# Schematic.net
KiCad netlist of a schematic drawn in Altium Designer
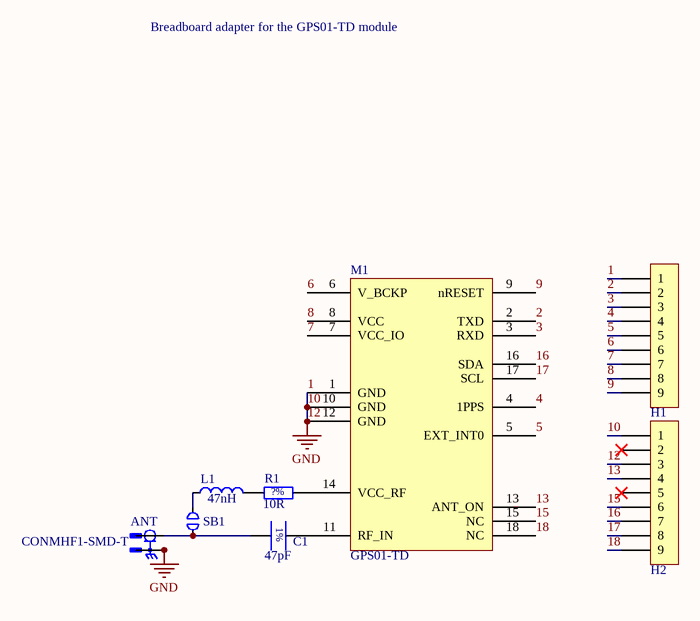
[diagram p0: Schematic.SchDoc]

(export (version "E")
  (design (tool "Eeschema 10.0.6"))
  (components
    (comp (ref "ANT")
      (value "CONMHF1-SMD-T")
      (footprint "TE_CONMHF1-SMD-T")
      (libsource (lib "CONMHF1-SMD-T") (part "CONMHF1-SMD-T"))
    )
    (comp (ref "C1")
      (value "47pF")
      (footprint "CAPACITOR_0805_2012M-70N")
      (description "Passive - Capacitor, Generic")
      (fields (field (name "TOLERANCE") "1%"))
      (libsource (lib "APSS Generic Components") (part "Generic Capacitor"))
    )
    (comp (ref "H1")
      (value "HDR,2.54mm,1x9")
      (footprint "APSS Connectors:HEADER_2.54MM_1x9PIN")
      (description "Connector - 2.54mm, 1x9-pin")
      (libsource (lib "APSS Connectors") (part "HDR,2.54mm,1x9"))
    )
    (comp (ref "H2")
      (value "HDR,2.54mm,1x9")
      (footprint "APSS Connectors:HEADER_2.54MM_1x9PIN")
      (description "Connector - 2.54mm, 1x9-pin")
      (libsource (lib "APSS Connectors") (part "HDR,2.54mm,1x9"))
    )
    (comp (ref "L1")
      (value "47nH")
      (footprint "APSS Generic Components:RESISTOR_0805_2012M-50N")
      (description "Passive - Inductor, Generic")
      (libsource (lib "APSS Generic Components") (part "Generic Inductor"))
    )
    (comp (ref "M1")
      (value "GPS01-TD")
      (footprint "GPS01-TD:GPS01-TD")
      (libsource (lib "GPS01-TD") (part "GPS01-TD"))
    )
    (comp (ref "R1")
      (value "10R")
      (footprint "RESISTOR_0805_2012M-50N")
      (description "Passive - Resistor, Generic")
      (fields (field (name "TOLERANCE") "?%"))
      (libsource (lib "APSS Generic Components") (part "Generic Resistor"))
    )
    (comp (ref "SB1")
      (value "Solder Jumper Normally Open")
      (footprint "APSS Generic Components:Solder Bridge Chevron 0402 Open")
      (libsource (lib "APSS Generic Components") (part "Solder Jumper Normally Open"))
    )
  )
  (nets
    (net (code "1") (name "/2") (class "Default")
      (node (ref "H1") (pin "2") (pinfunction "2_2") (pintype "passive"))
      (node (ref "M1") (pin "2") (pinfunction "TXD_2") (pintype "passive"))
    )
    (net (code "2") (name "/3") (class "Default")
      (node (ref "H1") (pin "3") (pinfunction "3_3") (pintype "passive"))
      (node (ref "M1") (pin "3") (pinfunction "RXD_3") (pintype "passive"))
    )
    (net (code "3") (name "/4") (class "Default")
      (node (ref "H1") (pin "4") (pinfunction "4_4") (pintype "passive"))
      (node (ref "M1") (pin "4") (pinfunction "1PPS_4") (pintype "passive"))
    )
    (net (code "4") (name "/5") (class "Default")
      (node (ref "H1") (pin "5") (pinfunction "5_5") (pintype "passive"))
      (node (ref "M1") (pin "5") (pinfunction "EXT_INT0_5") (pintype "passive"))
    )
    (net (code "5") (name "/6") (class "Default")
      (node (ref "H1") (pin "6") (pinfunction "6_6") (pintype "passive"))
      (node (ref "M1") (pin "6") (pinfunction "V_BCKP_6") (pintype "passive"))
    )
    (net (code "6") (name "/7") (class "Default")
      (node (ref "H1") (pin "7") (pinfunction "7_7") (pintype "passive"))
      (node (ref "M1") (pin "7") (pinfunction "VCC_IO_7") (pintype "passive"))
    )
    (net (code "7") (name "/8") (class "Default")
      (node (ref "H1") (pin "8") (pinfunction "8_8") (pintype "passive"))
      (node (ref "M1") (pin "8") (pinfunction "VCC_8") (pintype "passive"))
    )
    (net (code "8") (name "/9") (class "Default")
      (node (ref "H1") (pin "9") (pinfunction "9_9") (pintype "passive"))
      (node (ref "M1") (pin "9") (pinfunction "nRESET_9") (pintype "passive"))
    )
    (net (code "9") (name "/13") (class "Default")
      (node (ref "H2") (pin "4") (pinfunction "4_4") (pintype "passive"))
      (node (ref "M1") (pin "13") (pinfunction "ANT_ON_13") (pintype "passive"))
    )
    (net (code "10") (name "/15") (class "Default")
      (node (ref "H2") (pin "6") (pinfunction "6_6") (pintype "passive"))
      (node (ref "M1") (pin "15") (pinfunction "NC_15") (pintype "passive"))
    )
    (net (code "11") (name "/16") (class "Default")
      (node (ref "H2") (pin "7") (pinfunction "7_7") (pintype "passive"))
      (node (ref "M1") (pin "16") (pinfunction "SDA_16") (pintype "passive"))
    )
    (net (code "12") (name "/17") (class "Default")
      (node (ref "H2") (pin "8") (pinfunction "8_8") (pintype "passive"))
      (node (ref "M1") (pin "17") (pinfunction "SCL_17") (pintype "passive"))
    )
    (net (code "13") (name "/18") (class "Default")
      (node (ref "H2") (pin "9") (pinfunction "9_9") (pintype "passive"))
      (node (ref "M1") (pin "18") (pinfunction "NC_18") (pintype "passive"))
    )
    (net (code "14") (name "GND") (class "Default")
      (node (ref "ANT") (pin "2") (pinfunction "GND_2") (pintype "power_in"))
      (node (ref "ANT") (pin "3") (pinfunction "GND_3") (pintype "power_in"))
      (node (ref "ANT") (pin "4") (pinfunction "GND_4") (pintype "power_in"))
      (node (ref "H1") (pin "1") (pinfunction "1_1") (pintype "passive"))
      (node (ref "H2") (pin "1") (pinfunction "1_1") (pintype "passive"))
      (node (ref "H2") (pin "3") (pinfunction "3_3") (pintype "passive"))
      (node (ref "M1") (pin "1") (pinfunction "GND_1") (pintype "passive"))
      (node (ref "M1") (pin "10") (pinfunction "GND_10") (pintype "passive"))
      (node (ref "M1") (pin "12") (pinfunction "GND_12") (pintype "passive"))
    )
    (net (code "15") (name "Net-(ANT-SIG)") (class "Default")
      (node (ref "ANT") (pin "1") (pinfunction "SIG_1") (pintype "passive"))
      (node (ref "C1") (pin "1") (pinfunction "1_1") (pintype "passive"))
      (node (ref "SB1") (pin "2") (pinfunction "2_2") (pintype "passive"))
    )
    (net (code "16") (name "Net-(L1-Pad1)") (class "Default")
      (node (ref "L1") (pin "1") (pinfunction "1_1") (pintype "passive"))
      (node (ref "SB1") (pin "1") (pinfunction "1_1") (pintype "passive"))
    )
    (net (code "17") (name "Net-(L1-Pad2)") (class "Default")
      (node (ref "L1") (pin "2") (pinfunction "2_2") (pintype "passive"))
      (node (ref "R1") (pin "1") (pinfunction "1_1") (pintype "passive"))
    )
    (net (code "18") (name "Net-(M1-RF_IN)") (class "Default")
      (node (ref "C1") (pin "2") (pinfunction "2_2") (pintype "passive"))
      (node (ref "M1") (pin "11") (pinfunction "RF_IN_11") (pintype "passive"))
    )
    (net (code "19") (name "Net-(M1-VCC_RF)") (class "Default")
      (node (ref "M1") (pin "14") (pinfunction "VCC_RF_14") (pintype "passive"))
      (node (ref "R1") (pin "2") (pinfunction "2_2") (pintype "passive"))
    )
    (net (code "20") (name "unconnected-(H2-Pad2)") (class "Default")
      (node (ref "H2") (pin "2") (pinfunction "2_2") (pintype "passive+no_connect"))
    )
    (net (code "21") (name "unconnected-(H2-Pad5)") (class "Default")
      (node (ref "H2") (pin "5") (pinfunction "5_5") (pintype "passive+no_connect"))
    )
  )
)
